# dc_power_backup_module_v1.net
KiCad netlist of a schematic drawn in Altium Designer
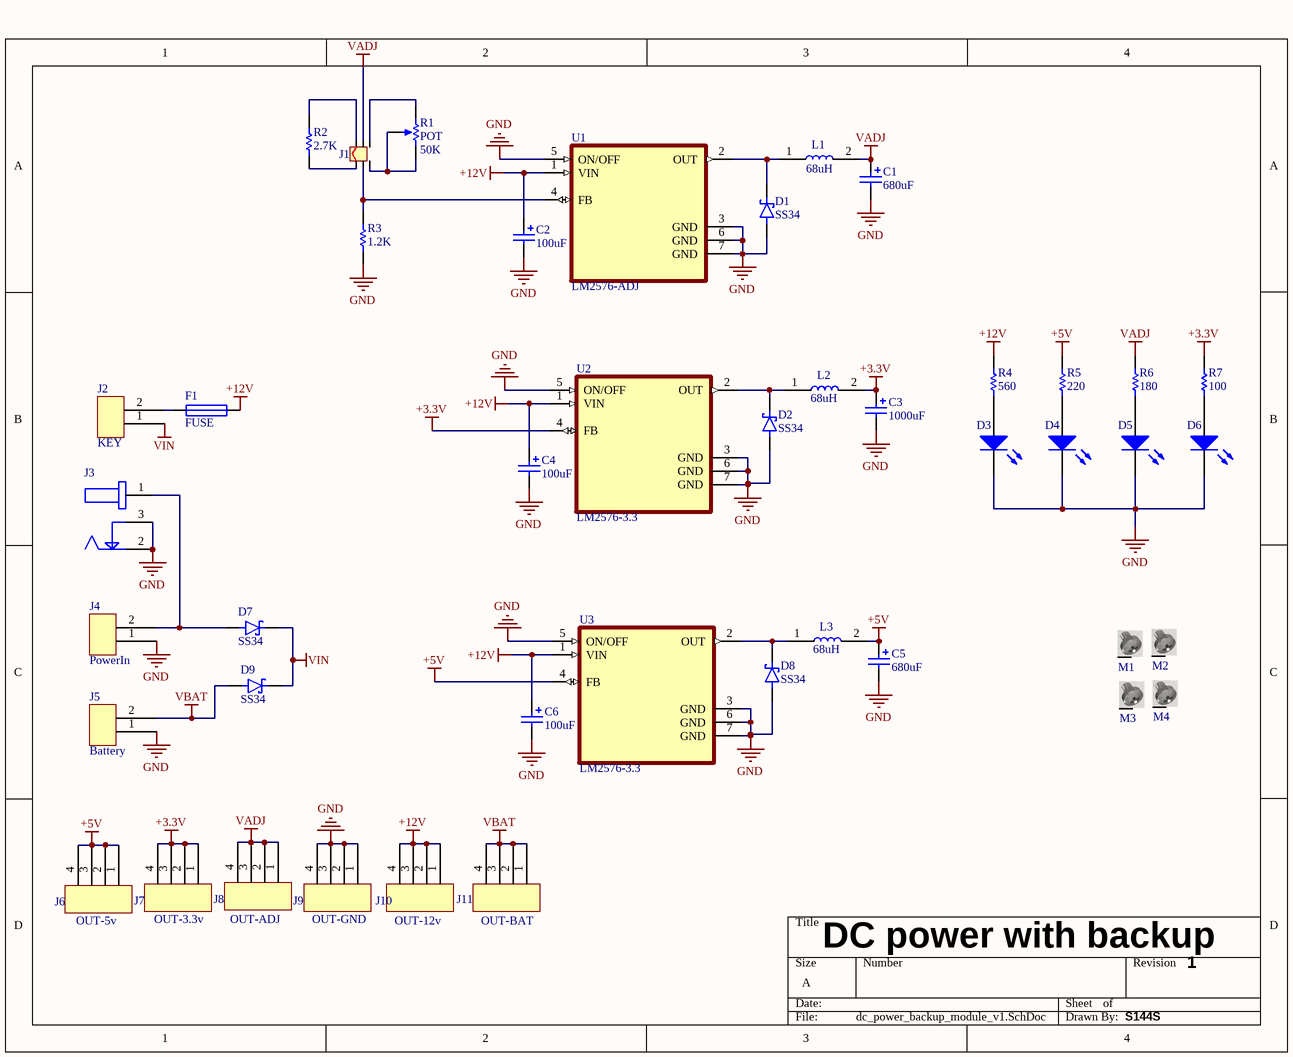
[diagram p0: dc_power_backup_module_v1.SchDoc]

(export (version "E")
  (design (tool "Eeschema 10.0.6"))
  (components
    (comp (ref "C1")
      (value "680uF")
      (footprint "Cap 03")
      (description "Polarized Capacitor (Axial)")
      (fields (field (name "Comment") "Cap Pol2") (field (name "PUBLISHER") "Altium Limited"))
      (libsource (lib "Miscellaneous Devices") (part "Cap Pol2"))
    )
    (comp (ref "C2")
      (value "100uF")
      (footprint "Cap - 470uF")
      (description "Polarized Capacitor (Axial)")
      (fields (field (name "Comment") "Cap Pol2") (field (name "PUBLISHER") "Altium Limited"))
      (libsource (lib "Miscellaneous Devices") (part "Cap Pol2"))
    )
    (comp (ref "C3")
      (value "1000uF")
      (footprint "Cap 04")
      (description "Polarized Capacitor (Axial)")
      (fields (field (name "Comment") "Cap Pol2") (field (name "PUBLISHER") "Altium Limited"))
      (libsource (lib "Miscellaneous Devices") (part "Cap Pol2"))
    )
    (comp (ref "C4")
      (value "100uF")
      (footprint "Cap - 470uF")
      (description "Polarized Capacitor (Axial)")
      (fields (field (name "Comment") "Cap Pol2") (field (name "PUBLISHER") "Altium Limited"))
      (libsource (lib "Miscellaneous Devices") (part "Cap Pol2"))
    )
    (comp (ref "C5")
      (value "680uF")
      (footprint "Cap 03")
      (description "Polarized Capacitor (Axial)")
      (fields (field (name "Comment") "Cap Pol2") (field (name "PUBLISHER") "Altium Limited"))
      (libsource (lib "Miscellaneous Devices") (part "Cap Pol2"))
    )
    (comp (ref "C6")
      (value "100uF")
      (footprint "Cap - 470uF")
      (description "Polarized Capacitor (Axial)")
      (fields (field (name "Comment") "Cap Pol2") (field (name "PUBLISHER") "Altium Limited"))
      (libsource (lib "Miscellaneous Devices") (part "Cap Pol2"))
    )
    (comp (ref "D1")
      (value "SS34")
      (footprint "DIOM7959X265N")
      (description "Diode Schottky 40V 3A Surface Mount DO-214AB _SMC_")
      (fields (field (name "MP") "SS34-E3/57T") (field (name "MF") "Vishay"))
      (libsource (lib "SS34-AB") (part "SS34-E3/57T"))
    )
    (comp (ref "D2")
      (value "SS34")
      (footprint "DIOM7959X265N")
      (description "Diode Schottky 40V 3A Surface Mount DO-214AB _SMC_")
      (fields (field (name "MP") "SS34-E3/57T") (field (name "MF") "Vishay"))
      (libsource (lib "SS34-AB") (part "SS34-E3/57T"))
    )
    (comp (ref "D3")
      (value "LED1")
      (footprint "LED SMD 1206")
      (description "Typical RED GaAs LED")
      (fields (field (name "PUBLISHER") "Altium Limited"))
      (libsource (lib "Miscellaneous Devices") (part "LED1"))
    )
    (comp (ref "D4")
      (value "LED1")
      (footprint "LED SMD 1206")
      (description "Typical RED GaAs LED")
      (fields (field (name "PUBLISHER") "Altium Limited"))
      (libsource (lib "Miscellaneous Devices") (part "LED1"))
    )
    (comp (ref "D5")
      (value "LED1")
      (footprint "LED SMD 1206")
      (description "Typical RED GaAs LED")
      (fields (field (name "PUBLISHER") "Altium Limited"))
      (libsource (lib "Miscellaneous Devices") (part "LED1"))
    )
    (comp (ref "D6")
      (value "LED1")
      (footprint "LED SMD 1206")
      (description "Typical RED GaAs LED")
      (fields (field (name "PUBLISHER") "Altium Limited"))
      (libsource (lib "Miscellaneous Devices") (part "LED1"))
    )
    (comp (ref "D7")
      (value "SS34")
      (footprint "DIOM7959X265N")
      (description "Diode Schottky 40V 3A Surface Mount DO-214AB _SMC_")
      (fields (field (name "MP") "SS34-E3/57T") (field (name "MF") "Vishay"))
      (libsource (lib "SS34-AB") (part "SS34-E3/57T"))
    )
    (comp (ref "D8")
      (value "SS34")
      (footprint "DIOM7959X265N")
      (description "Diode Schottky 40V 3A Surface Mount DO-214AB _SMC_")
      (fields (field (name "MP") "SS34-E3/57T") (field (name "MF") "Vishay"))
      (libsource (lib "SS34-AB") (part "SS34-E3/57T"))
    )
    (comp (ref "D9")
      (value "SS34")
      (footprint "DIOM7959X265N")
      (description "Diode Schottky 40V 3A Surface Mount DO-214AB _SMC_")
      (fields (field (name "MP") "SS34-E3/57T") (field (name "MF") "Vishay"))
      (libsource (lib "SS34-AB") (part "SS34-E3/57T"))
    )
    (comp (ref "F1") (value "FUSE") (footprint "Fuse - Complex") (libsource (lib "JJ_S1") (part "FUSE")))
    (comp (ref "J1")
      (value "JUMPER6")
      (footprint "JUMP6")
      (description "Ju,per & dip Switch")
      (libsource (lib "JJ_S1") (part "JUMPER6"))
    )
    (comp (ref "J2") (value "KEY") (footprint "SIP2") (libsource (lib "JJ_S1") (part "2PIN")))
    (comp (ref "J3")
      (value "DCJ250-10-A_XX-X_REVA")
      (footprint "Power Jack")
      (description "Power Barrel Connector Jack 2.55mm ID _0.100_, 5.50mm OD _0.217_ Through Hole, Right Angle")
      (fields (field (name "MP") "DCJ250-10-A-K1-K") (field (name "MF") "Global Connector Technology"))
      (libsource (lib "Power-Jack") (part "DCJ250-10-A_XX-X_REVA"))
    )
    (comp (ref "J4") (value "PowerIn") (footprint "SIP2") (libsource (lib "JJ_S1") (part "2PIN")))
    (comp (ref "J5") (value "Battery") (footprint "SIP2") (libsource (lib "JJ_S1") (part "2PIN")))
    (comp (ref "J6") (value "OUT-5v") (footprint "SIP4") (libsource (lib "JJ_S1") (part "4PIN")))
    (comp (ref "J7") (value "OUT-3.3v") (footprint "SIP4") (libsource (lib "JJ_S1") (part "4PIN")))
    (comp (ref "J8") (value "OUT-ADJ") (footprint "SIP4") (libsource (lib "JJ_S1") (part "4PIN")))
    (comp (ref "J9") (value "OUT-GND") (footprint "SIP4") (libsource (lib "JJ_S1") (part "4PIN")))
    (comp (ref "J10") (value "OUT-12v") (footprint "SIP4") (libsource (lib "JJ_S1") (part "4PIN")))
    (comp (ref "J11") (value "OUT-BAT") (footprint "SIP4") (libsource (lib "JJ_S1") (part "4PIN")))
    (comp (ref "L1")
      (value "68uH")
      (footprint "*IND_SRP1265A-330M")
      (description "Inductor Power Shielded Wirewound 33uH 20% 100KHz Carbonyl Powder 8A 58mOhm DCR Automotive T/R")
      (fields (field (name "MF") "Bourns") (field (name "MP") "SRP1265A-330M"))
      (libsource (lib "33uH-Inductor") (part "SRP1265A-330M"))
    )
    (comp (ref "L2")
      (value "68uH")
      (footprint "*IND_SRP1265A-330M")
      (description "Inductor Power Shielded Wirewound 33uH 20% 100KHz Carbonyl Powder 8A 58mOhm DCR Automotive T/R")
      (fields (field (name "MF") "Bourns") (field (name "MP") "SRP1265A-330M"))
      (libsource (lib "33uH-Inductor") (part "SRP1265A-330M"))
    )
    (comp (ref "L3")
      (value "68uH")
      (footprint "*IND_SRP1265A-330M")
      (description "Inductor Power Shielded Wirewound 33uH 20% 100KHz Carbonyl Powder 8A 58mOhm DCR Automotive T/R")
      (fields (field (name "MF") "Bourns") (field (name "MP") "SRP1265A-330M"))
      (libsource (lib "33uH-Inductor") (part "SRP1265A-330M"))
    )
    (comp (ref "M1")
      (value "Screw")
      (footprint "Board Screw_No Silk")
      (description "Board Screw With Spacer")
      (libsource (lib "JJ_S1") (part "Board Screw"))
    )
    (comp (ref "M2")
      (value "Screw")
      (footprint "Board Screw_No Silk")
      (description "Board Screw With Spacer")
      (libsource (lib "JJ_S1") (part "Board Screw"))
    )
    (comp (ref "M3")
      (value "Screw")
      (footprint "Board Screw_No Silk")
      (description "Board Screw With Spacer")
      (libsource (lib "JJ_S1") (part "Board Screw"))
    )
    (comp (ref "M4")
      (value "Screw")
      (footprint "Board Screw_No Silk")
      (description "Board Screw With Spacer")
      (libsource (lib "JJ_S1") (part "Board Screw"))
    )
    (comp (ref "R1")
      (value "POT")
      (footprint "Pot 00")
      (description "Volume Potentiometer")
      (fields (field (name "ALTIUM_VALUE") "50K") (field (name "PUBLISHER") "Altium Limited"))
      (libsource (lib "Ario Electronics ALTLIB") (part "RPot"))
    )
    (comp (ref "R2")
      (value "2.7K")
      (footprint "RES 1206")
      (description "Resistor")
      (fields (field (name "Comment") "Res-1206") (field (name "PUBLISHER") "Altium Limited"))
      (libsource (lib "Ario Electronics ALTLIB") (part "Res-1206"))
    )
    (comp (ref "R3")
      (value "1.2K")
      (footprint "RES 1206")
      (description "Resistor")
      (fields (field (name "Comment") "Res-1206") (field (name "PUBLISHER") "Altium Limited"))
      (libsource (lib "Ario Electronics ALTLIB") (part "Res-1206"))
    )
    (comp (ref "R4")
      (value "560")
      (footprint "RES 1206")
      (description "Resistor")
      (fields (field (name "Comment") "Res-1206") (field (name "PUBLISHER") "Altium Limited"))
      (libsource (lib "Ario Electronics ALTLIB") (part "Res-1206"))
    )
    (comp (ref "R5")
      (value "220")
      (footprint "RES 1206")
      (description "Resistor")
      (fields (field (name "Comment") "Res-1206") (field (name "PUBLISHER") "Altium Limited"))
      (libsource (lib "Ario Electronics ALTLIB") (part "Res-1206"))
    )
    (comp (ref "R6")
      (value "180")
      (footprint "RES 1206")
      (description "Resistor")
      (fields (field (name "Comment") "Res-1206") (field (name "PUBLISHER") "Altium Limited"))
      (libsource (lib "Ario Electronics ALTLIB") (part "Res-1206"))
    )
    (comp (ref "R7")
      (value "100")
      (footprint "RES 1206")
      (description "Resistor")
      (fields (field (name "Comment") "Res-1206") (field (name "PUBLISHER") "Altium Limited"))
      (libsource (lib "Ario Electronics ALTLIB") (part "Res-1206"))
    )
    (comp (ref "U1")
      (value "LM2576-ADJ")
      (footprint "VREG_TPS79625KTTR")
      (fields
        (field (name "MP") "LM2576HVS-ADJ/NOPB")
        (field (name "MF") "Texas Instruments")
        (field (name "BUYPART") "https://www.snapeda.com/parts/LM2576HVS-ADJ/NOPB/Texas%20Instruments/view-part/213619/?ref=eda")
      )
      (libsource (lib "LM2576HVS-ADJ_NOPB") (part "LM2576HVS-ADJ/NOPB"))
    )
    (comp (ref "U2")
      (value "LM2576-3.3")
      (footprint "VREG_TPS79625KTTR")
      (fields
        (field (name "MP") "LM2576HVS-ADJ/NOPB")
        (field (name "MF") "Texas Instruments")
        (field (name "BUYPART") "https://www.snapeda.com/parts/LM2576HVS-ADJ/NOPB/Texas%20Instruments/view-part/213619/?ref=eda")
      )
      (libsource (lib "LM2576HVS-ADJ_NOPB") (part "LM2576HVS-ADJ/NOPB"))
    )
    (comp (ref "U3")
      (value "LM2576-3.3")
      (footprint "VREG_TPS79625KTTR")
      (fields
        (field (name "MP") "LM2576HVS-ADJ/NOPB")
        (field (name "MF") "Texas Instruments")
        (field (name "BUYPART") "https://www.snapeda.com/parts/LM2576HVS-ADJ/NOPB/Texas%20Instruments/view-part/213619/?ref=eda")
      )
      (libsource (lib "LM2576HVS-ADJ_NOPB") (part "LM2576HVS-ADJ/NOPB"))
    )
  )
  (nets
    (net (code "1") (name "+3.3V") (class "Default")
      (node (ref "C3") (pin "1") (pinfunction "1_1") (pintype "passive"))
      (node (ref "J7") (pin "1") (pintype "passive"))
      (node (ref "J7") (pin "2") (pintype "passive"))
      (node (ref "J7") (pin "3") (pintype "passive"))
      (node (ref "J7") (pin "4") (pintype "passive"))
      (node (ref "L2") (pin "2") (pinfunction "2_2") (pintype "passive"))
      (node (ref "R7") (pin "2") (pinfunction "2_2") (pintype "passive"))
      (node (ref "U2") (pin "4") (pinfunction "FB_4") (pintype "bidirectional"))
    )
    (net (code "2") (name "+5V") (class "Default")
      (node (ref "C5") (pin "1") (pinfunction "1_1") (pintype "passive"))
      (node (ref "J6") (pin "1") (pintype "passive"))
      (node (ref "J6") (pin "2") (pintype "passive"))
      (node (ref "J6") (pin "3") (pintype "passive"))
      (node (ref "J6") (pin "4") (pintype "passive"))
      (node (ref "L3") (pin "2") (pinfunction "2_2") (pintype "passive"))
      (node (ref "R5") (pin "2") (pinfunction "2_2") (pintype "passive"))
      (node (ref "U3") (pin "4") (pinfunction "FB_4") (pintype "bidirectional"))
    )
    (net (code "3") (name "+12V") (class "Default")
      (node (ref "C2") (pin "1") (pinfunction "1_1") (pintype "passive"))
      (node (ref "C4") (pin "1") (pinfunction "1_1") (pintype "passive"))
      (node (ref "C6") (pin "1") (pinfunction "1_1") (pintype "passive"))
      (node (ref "F1") (pin "2") (pintype "passive"))
      (node (ref "J10") (pin "1") (pintype "passive"))
      (node (ref "J10") (pin "2") (pintype "passive"))
      (node (ref "J10") (pin "3") (pintype "passive"))
      (node (ref "J10") (pin "4") (pintype "passive"))
      (node (ref "R4") (pin "2") (pinfunction "2_2") (pintype "passive"))
      (node (ref "U1") (pin "1") (pinfunction "VIN_1") (pintype "input"))
      (node (ref "U2") (pin "1") (pinfunction "VIN_1") (pintype "input"))
      (node (ref "U3") (pin "1") (pinfunction "VIN_1") (pintype "input"))
    )
    (net (code "4") (name "GND") (class "Default")
      (node (ref "C1") (pin "2") (pinfunction "2_2") (pintype "passive"))
      (node (ref "C2") (pin "2") (pinfunction "2_2") (pintype "passive"))
      (node (ref "C3") (pin "2") (pinfunction "2_2") (pintype "passive"))
      (node (ref "C4") (pin "2") (pinfunction "2_2") (pintype "passive"))
      (node (ref "C5") (pin "2") (pinfunction "2_2") (pintype "passive"))
      (node (ref "C6") (pin "2") (pinfunction "2_2") (pintype "passive"))
      (node (ref "D1") (pin "A") (pinfunction "A_A") (pintype "passive"))
      (node (ref "D2") (pin "A") (pinfunction "A_A") (pintype "passive"))
      (node (ref "D3") (pin "2") (pinfunction "K_2") (pintype "passive"))
      (node (ref "D4") (pin "2") (pinfunction "K_2") (pintype "passive"))
      (node (ref "D5") (pin "2") (pinfunction "K_2") (pintype "passive"))
      (node (ref "D6") (pin "2") (pinfunction "K_2") (pintype "passive"))
      (node (ref "D8") (pin "A") (pinfunction "A_A") (pintype "passive"))
      (node (ref "J3") (pin "2") (pinfunction "2_2") (pintype "passive"))
      (node (ref "J3") (pin "3") (pinfunction "3_3") (pintype "passive"))
      (node (ref "J4") (pin "1") (pintype "passive"))
      (node (ref "J5") (pin "1") (pintype "passive"))
      (node (ref "J9") (pin "1") (pintype "passive"))
      (node (ref "J9") (pin "2") (pintype "passive"))
      (node (ref "J9") (pin "3") (pintype "passive"))
      (node (ref "J9") (pin "4") (pintype "passive"))
      (node (ref "R3") (pin "1") (pinfunction "1_1") (pintype "passive"))
      (node (ref "U1") (pin "3") (pinfunction "GND_3") (pintype "power_in"))
      (node (ref "U1") (pin "5") (pinfunction "ON/OFF_5") (pintype "input"))
      (node (ref "U1") (pin "6") (pinfunction "GND_6") (pintype "power_in"))
      (node (ref "U1") (pin "7") (pinfunction "GND_7") (pintype "power_in"))
      (node (ref "U2") (pin "3") (pinfunction "GND_3") (pintype "power_in"))
      (node (ref "U2") (pin "5") (pinfunction "ON/OFF_5") (pintype "input"))
      (node (ref "U2") (pin "6") (pinfunction "GND_6") (pintype "power_in"))
      (node (ref "U2") (pin "7") (pinfunction "GND_7") (pintype "power_in"))
      (node (ref "U3") (pin "3") (pinfunction "GND_3") (pintype "power_in"))
      (node (ref "U3") (pin "5") (pinfunction "ON/OFF_5") (pintype "input"))
      (node (ref "U3") (pin "6") (pinfunction "GND_6") (pintype "power_in"))
      (node (ref "U3") (pin "7") (pinfunction "GND_7") (pintype "power_in"))
    )
    (net (code "5") (name "Net-(D3-A)") (class "Default")
      (node (ref "D3") (pin "1") (pinfunction "A_1") (pintype "passive"))
      (node (ref "R4") (pin "1") (pinfunction "1_1") (pintype "passive"))
    )
    (net (code "6") (name "Net-(D4-A)") (class "Default")
      (node (ref "D4") (pin "1") (pinfunction "A_1") (pintype "passive"))
      (node (ref "R5") (pin "1") (pinfunction "1_1") (pintype "passive"))
    )
    (net (code "7") (name "Net-(D5-A)") (class "Default")
      (node (ref "D5") (pin "1") (pinfunction "A_1") (pintype "passive"))
      (node (ref "R6") (pin "1") (pinfunction "1_1") (pintype "passive"))
    )
    (net (code "8") (name "Net-(D6-A)") (class "Default")
      (node (ref "D6") (pin "1") (pinfunction "A_1") (pintype "passive"))
      (node (ref "R7") (pin "1") (pinfunction "1_1") (pintype "passive"))
    )
    (net (code "9") (name "Net-(D7-PadA)") (class "Default")
      (node (ref "D7") (pin "A") (pinfunction "A_A") (pintype "passive"))
      (node (ref "J3") (pin "1") (pinfunction "1_1") (pintype "passive"))
      (node (ref "J4") (pin "2") (pintype "passive"))
    )
    (net (code "10") (name "Net-(F1-Pad1)") (class "Default")
      (node (ref "F1") (pin "1") (pintype "passive"))
      (node (ref "J2") (pin "2") (pintype "passive"))
    )
    (net (code "11") (name "Net-(J1-Pad1)") (class "Default")
      (node (ref "J1") (pin "1") (pintype "passive"))
      (node (ref "R2") (pin "1") (pinfunction "1_1") (pintype "passive"))
    )
    (net (code "12") (name "Net-(J1-Pad2)") (class "Default")
      (node (ref "J1") (pin "2") (pintype "passive"))
      (node (ref "R2") (pin "2") (pinfunction "2_2") (pintype "passive"))
    )
    (net (code "13") (name "Net-(R1-BOT)") (class "Default")
      (node (ref "J1") (pin "5") (pintype "passive"))
      (node (ref "R1") (pin "2") (pinfunction "BOT_2") (pintype "passive"))
      (node (ref "R1") (pin "3") (pinfunction "TAP_3") (pintype "passive"))
    )
    (net (code "14") (name "Net-(R1-TOP)") (class "Default")
      (node (ref "J1") (pin "6") (pintype "passive"))
      (node (ref "R1") (pin "1") (pinfunction "TOP_1") (pintype "passive"))
    )
    (net (code "15") (name "Net-(U1-FB)") (class "Default")
      (node (ref "J1") (pin "3") (pintype "passive"))
      (node (ref "R3") (pin "2") (pinfunction "2_2") (pintype "passive"))
      (node (ref "U1") (pin "4") (pinfunction "FB_4") (pintype "bidirectional"))
    )
    (net (code "16") (name "Net-(U1-OUT)") (class "Default")
      (node (ref "D1") (pin "C") (pinfunction "C_C") (pintype "passive"))
      (node (ref "L1") (pin "1") (pinfunction "1_1") (pintype "passive"))
      (node (ref "U1") (pin "2") (pinfunction "OUT_2") (pintype "output"))
    )
    (net (code "17") (name "Net-(U2-OUT)") (class "Default")
      (node (ref "D2") (pin "C") (pinfunction "C_C") (pintype "passive"))
      (node (ref "L2") (pin "1") (pinfunction "1_1") (pintype "passive"))
      (node (ref "U2") (pin "2") (pinfunction "OUT_2") (pintype "output"))
    )
    (net (code "18") (name "Net-(U3-OUT)") (class "Default")
      (node (ref "D8") (pin "C") (pinfunction "C_C") (pintype "passive"))
      (node (ref "L3") (pin "1") (pinfunction "1_1") (pintype "passive"))
      (node (ref "U3") (pin "2") (pinfunction "OUT_2") (pintype "output"))
    )
    (net (code "19") (name "VADJ") (class "Default")
      (node (ref "C1") (pin "1") (pinfunction "1_1") (pintype "passive"))
      (node (ref "J1") (pin "4") (pintype "passive"))
      (node (ref "J8") (pin "1") (pintype "passive"))
      (node (ref "J8") (pin "2") (pintype "passive"))
      (node (ref "J8") (pin "3") (pintype "passive"))
      (node (ref "J8") (pin "4") (pintype "passive"))
      (node (ref "L1") (pin "2") (pinfunction "2_2") (pintype "passive"))
      (node (ref "R6") (pin "2") (pinfunction "2_2") (pintype "passive"))
    )
    (net (code "20") (name "VBAT") (class "Default")
      (node (ref "D9") (pin "A") (pinfunction "A_A") (pintype "passive"))
      (node (ref "J11") (pin "1") (pintype "passive"))
      (node (ref "J11") (pin "2") (pintype "passive"))
      (node (ref "J11") (pin "3") (pintype "passive"))
      (node (ref "J11") (pin "4") (pintype "passive"))
      (node (ref "J5") (pin "2") (pintype "passive"))
    )
    (net (code "21") (name "VIN") (class "Default")
      (node (ref "D7") (pin "C") (pinfunction "C_C") (pintype "passive"))
      (node (ref "D9") (pin "C") (pinfunction "C_C") (pintype "passive"))
      (node (ref "J2") (pin "1") (pintype "passive"))
    )
    (net (code "22") (name "unconnected-(M1-PadS)") (class "Default")
      (node (ref "M1") (pin "S") (pinfunction "S_S") (pintype "passive"))
    )
    (net (code "23") (name "unconnected-(M2-PadS)") (class "Default")
      (node (ref "M2") (pin "S") (pinfunction "S_S") (pintype "passive"))
    )
    (net (code "24") (name "unconnected-(M3-PadS)") (class "Default")
      (node (ref "M3") (pin "S") (pinfunction "S_S") (pintype "passive"))
    )
    (net (code "25") (name "unconnected-(M4-PadS)") (class "Default")
      (node (ref "M4") (pin "S") (pinfunction "S_S") (pintype "passive"))
    )
  )
)
